# ap5724_6-boost-driver-mk-1_0.net
KiCad netlist of a schematic drawn in EAGLE
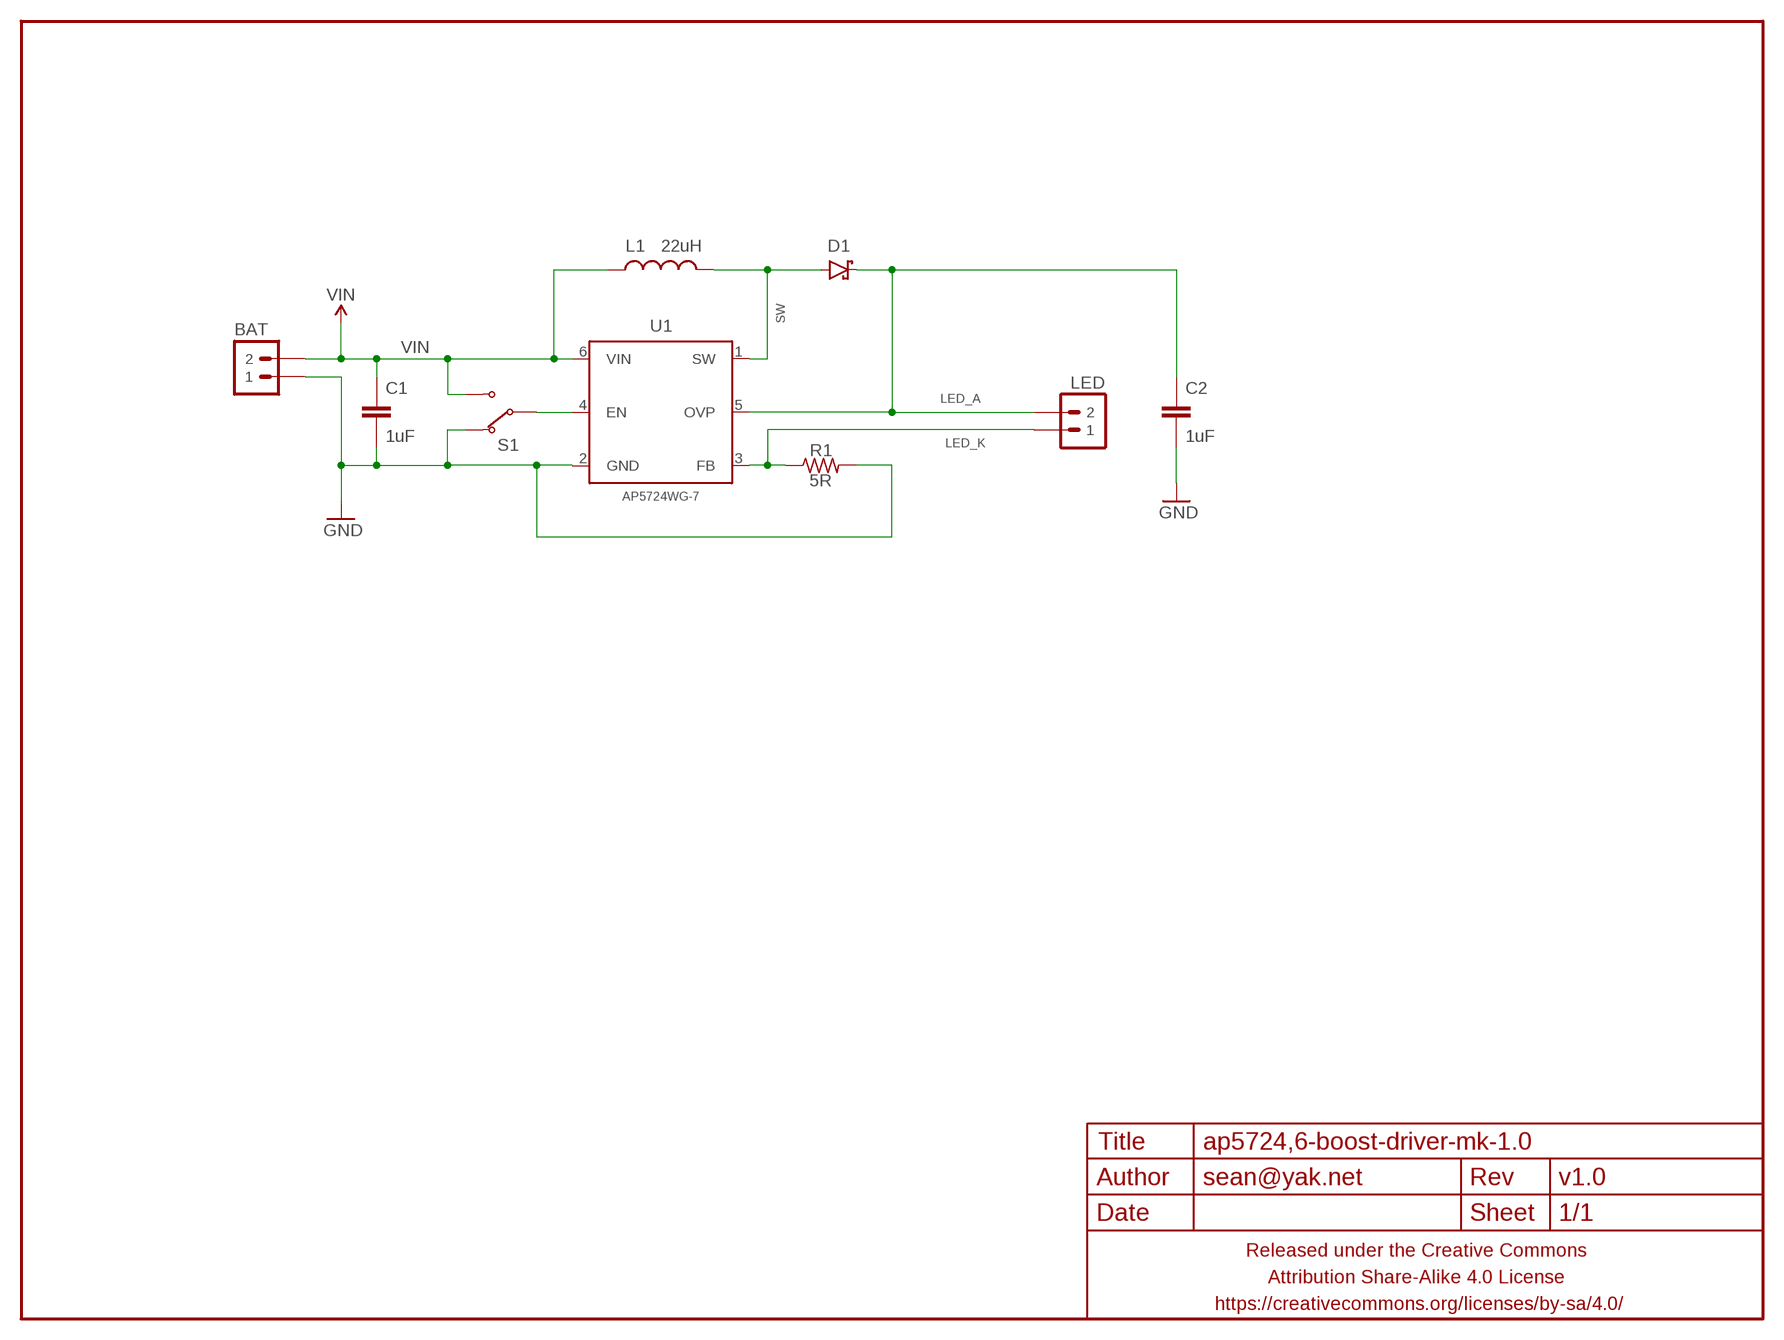
[diagram p0: schematic, sheet 1]

(export (version "E")
  (design (tool "Eeschema 10.0.6"))
  (components
    (comp (ref "BAT")
      (value "M02PTH-CENTERED")
      (footprint "eagle-import:1X02-CENTER")
      (libsource (lib "eagle-import") (part "M02PTH-CENTERED"))
    )
    (comp (ref "C1")
      (value "1uF")
      (footprint "eagle-import:C0603-TIGHTER")
      (libsource (lib "eagle-import") (part "CAPACITOR-CERAMICC0603-TIGHTER"))
    )
    (comp (ref "C2")
      (value "1uF")
      (footprint "eagle-import:C0603-TIGHTER")
      (libsource (lib "eagle-import") (part "CAPACITOR-CERAMICC0603-TIGHTER"))
    )
    (comp (ref "D1")
      (value "DIODE-SCHOTTKYSOD323")
      (footprint "eagle-import:SOD323-SCHOTTKY")
      (libsource (lib "eagle-import") (part "DIODE-SCHOTTKYSOD323"))
    )
    (comp (ref "FRAME1")
      (value "FRAME-LETTERNO_PACKAGE")
      (footprint "eagle-import:DUMMY")
      (fields (field (name "DESIGNER") "sean@yak.net") (field (name "VERSION") "v1.0"))
      (libsource (lib "eagle-import") (part "FRAME-LETTERNO_PACKAGE"))
    )
    (comp (ref "L1")
      (value "22uH")
      (footprint "eagle-import:L0603")
      (libsource (lib "eagle-import") (part "INDUCTOR0603-TIGHTER"))
    )
    (comp (ref "LED")
      (value "M02PTH-CENTERED")
      (footprint "eagle-import:1X02-CENTER")
      (libsource (lib "eagle-import") (part "M02PTH-CENTERED"))
    )
    (comp (ref "R1")
      (value "5R")
      (footprint "eagle-import:R0603-TIGHTER")
      (libsource (lib "eagle-import") (part "RESISTORR0603-TIGHTER"))
    )
    (comp (ref "S1")
      (value "SWITCH-SPDTJS102011SAQN")
      (footprint "eagle-import:SWITCH-SPDT-SMD-RA-JS102011SAQN")
      (libsource (lib "eagle-import") (part "SWITCH-SPDTJS102011SAQN"))
    )
    (comp (ref "U1")
      (value "AP5724WG-7")
      (footprint "eagle-import:SOT26")
      (libsource (lib "eagle-import") (part "AP5724,6SOT26"))
    )
  )
  (nets
    (net (code "1") (name "/LED_A") (class "Default")
      (node (ref "C2") (pin "1") (pinfunction "1_1") (pintype "passive"))
      (node (ref "D1") (pin "C") (pinfunction "C_C") (pintype "passive"))
      (node (ref "LED") (pin "2") (pinfunction "2_2") (pintype "passive"))
      (node (ref "U1") (pin "5") (pinfunction "OVP_5") (pintype "bidirectional"))
    )
    (net (code "2") (name "/LED_K") (class "Default")
      (node (ref "LED") (pin "1") (pinfunction "1_1") (pintype "passive"))
      (node (ref "R1") (pin "1") (pinfunction "1_1") (pintype "passive"))
      (node (ref "U1") (pin "3") (pinfunction "FB_3") (pintype "bidirectional"))
    )
    (net (code "3") (name "/SW") (class "Default")
      (node (ref "D1") (pin "A") (pinfunction "A_A") (pintype "passive"))
      (node (ref "L1") (pin "2") (pinfunction "2_2") (pintype "passive"))
      (node (ref "U1") (pin "1") (pinfunction "SW_1") (pintype "bidirectional"))
    )
    (net (code "4") (name "GND") (class "Default")
      (node (ref "BAT") (pin "1") (pinfunction "1_1") (pintype "passive"))
      (node (ref "C1") (pin "2") (pinfunction "2_2") (pintype "passive"))
      (node (ref "C2") (pin "2") (pinfunction "2_2") (pintype "passive"))
      (node (ref "R1") (pin "2") (pinfunction "2_2") (pintype "passive"))
      (node (ref "S1") (pin "3") (pinfunction "NC_3") (pintype "passive"))
      (node (ref "U1") (pin "2") (pinfunction "GND_2") (pintype "bidirectional"))
    )
    (net (code "5") (name "Net-(S1-COM)") (class "Default")
      (node (ref "S1") (pin "2") (pinfunction "COM_2") (pintype "passive"))
      (node (ref "U1") (pin "4") (pinfunction "EN_4") (pintype "bidirectional"))
    )
    (net (code "6") (name "VIN") (class "Default")
      (node (ref "BAT") (pin "2") (pinfunction "2_2") (pintype "passive"))
      (node (ref "C1") (pin "1") (pinfunction "1_1") (pintype "passive"))
      (node (ref "L1") (pin "1") (pinfunction "1_1") (pintype "passive"))
      (node (ref "S1") (pin "1") (pinfunction "NO_1") (pintype "passive"))
      (node (ref "U1") (pin "6") (pinfunction "VIN_6") (pintype "bidirectional"))
    )
  )
)
